# Extruder_Board2_0_0.net
KiCad netlist of a schematic drawn in EAGLE
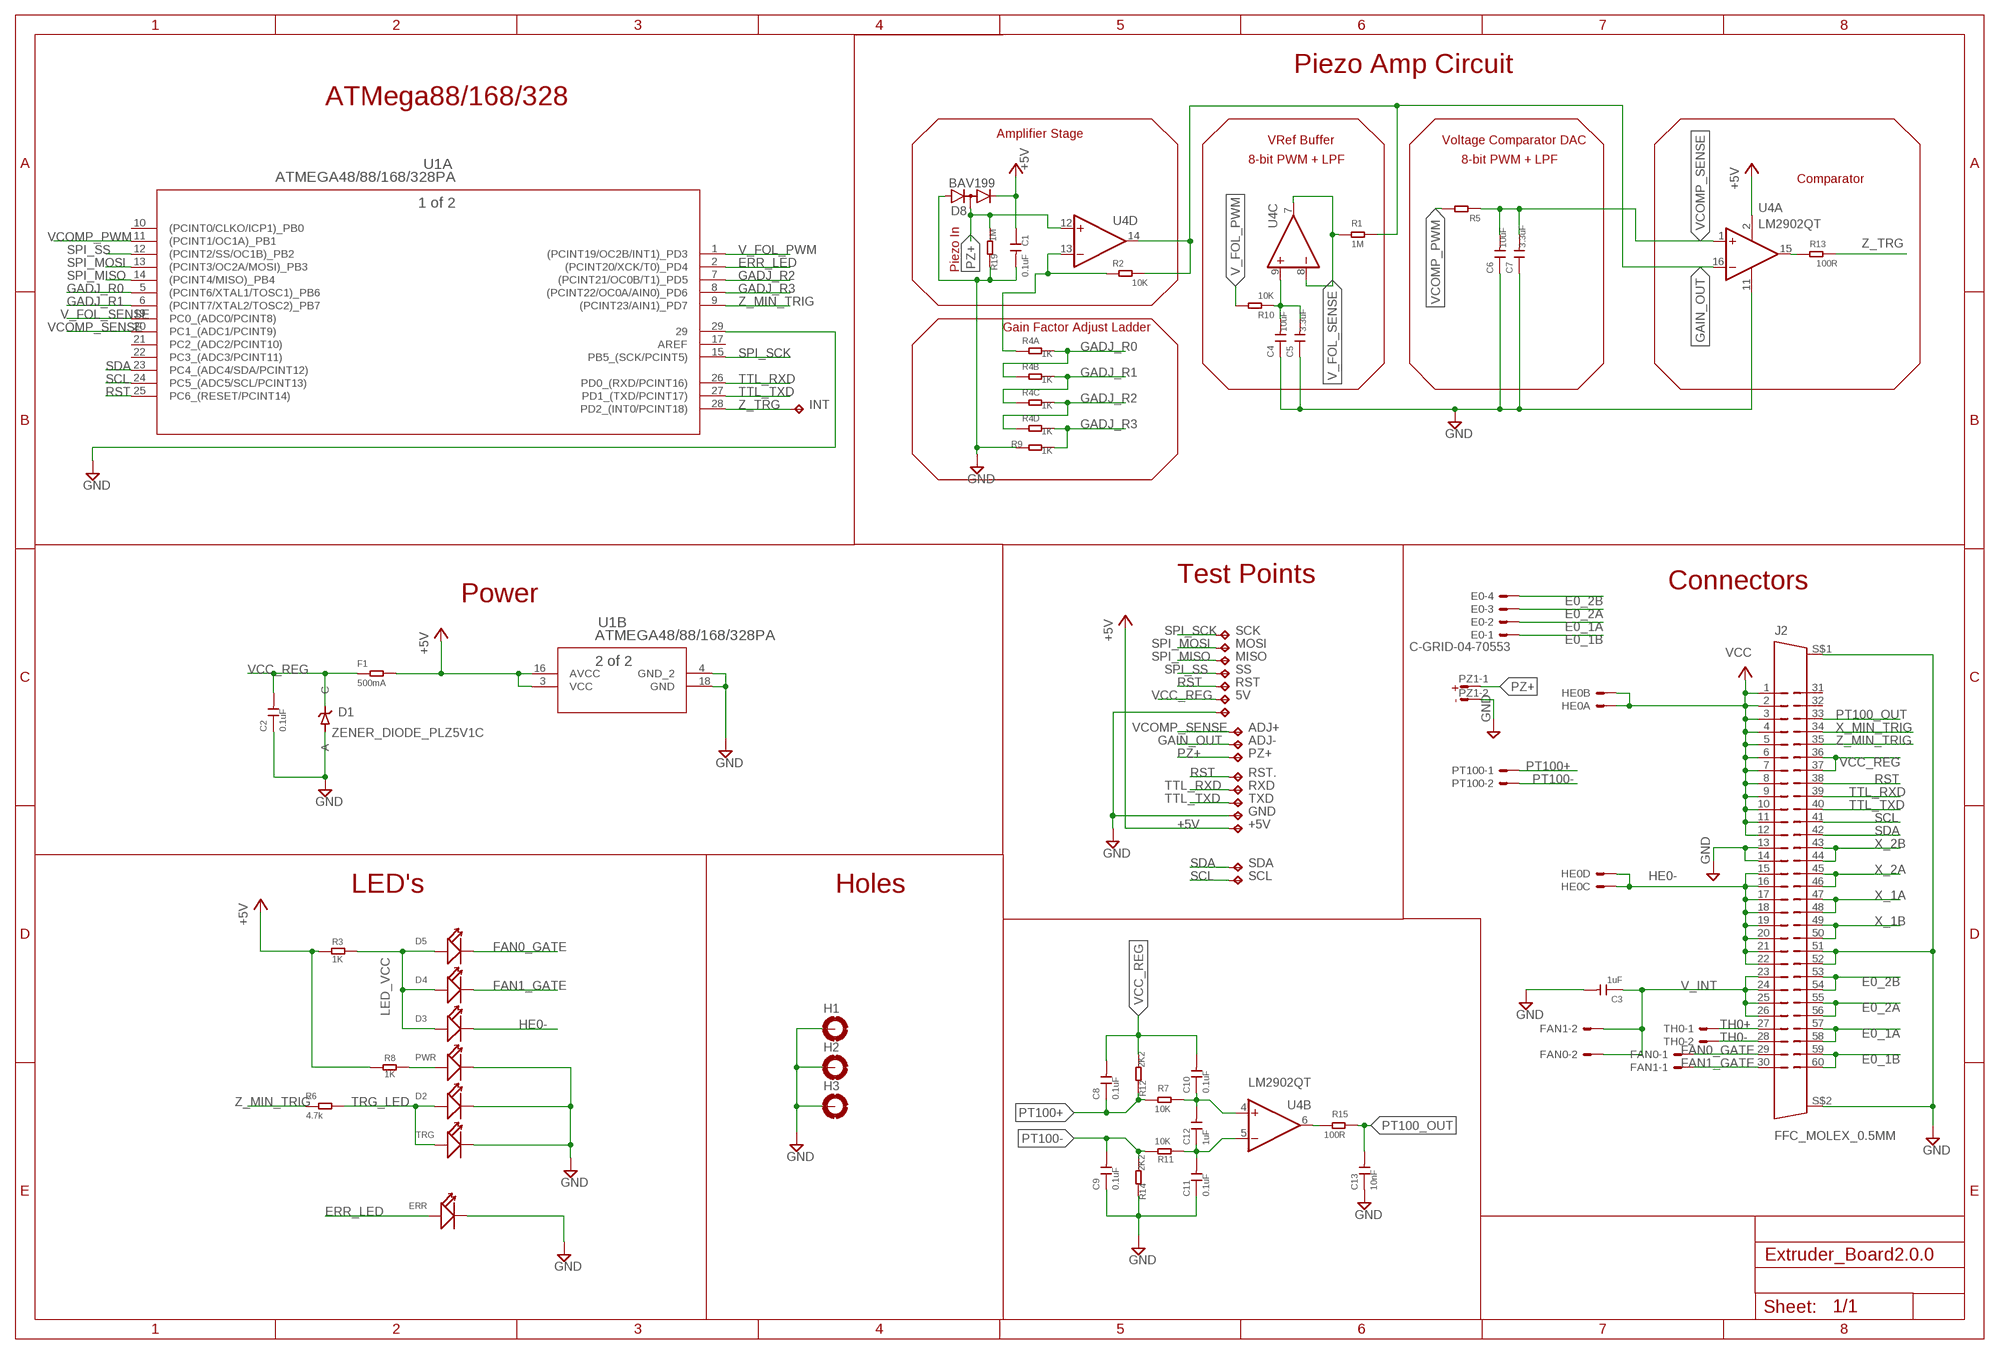
[diagram p0: schematic, sheet 1]

(export (version "E")
  (design (tool "Eeschema 10.0.6"))
  (components
    (comp (ref "+5V")
      (value "TPTP13SQ")
      (footprint "eagle-import:TP13SQ")
      (libsource (lib "eagle-import") (part "testpad_385_TPTP13SQ"))
    )
    (comp (ref "5V")
      (value "TPTP13SQ")
      (footprint "eagle-import:TP13SQ")
      (libsource (lib "eagle-import") (part "TPTP13SQ"))
    )
    (comp (ref "ADJ+")
      (value "TPTP13SQ")
      (footprint "eagle-import:TP13SQ")
      (libsource (lib "eagle-import") (part "TPTP13SQ"))
    )
    (comp (ref "ADJ-")
      (value "TPTP13SQ")
      (footprint "eagle-import:TP13SQ")
      (libsource (lib "eagle-import") (part "TPTP13SQ"))
    )
    (comp (ref "C1")
      (value "0.1uF")
      (footprint "eagle-import:CAPC1005X50")
      (libsource (lib "eagle-import") (part "CERAMIC-1NF-50V-10%-X7R(0402)CAP_0402"))
    )
    (comp (ref "C2")
      (value "0.1uF")
      (footprint "eagle-import:CAPC1005X50")
      (libsource (lib "eagle-import") (part "CERAMIC-1NF-50V-10%-X7R(0402)CAP_0402"))
    )
    (comp (ref "C3")
      (value "1uF")
      (footprint "eagle-import:CAPC1609X80")
      (libsource (lib "eagle-import") (part "SEEED-CAPACITOR_CERAMIC-10UF-25V-10%-X5R(0805)CAP_0603_GEN"))
    )
    (comp (ref "C4")
      (value "10uF")
      (footprint "eagle-import:CAPC1005X50")
      (libsource (lib "eagle-import") (part "CERAMIC-1NF-50V-10%-X7R(0402)CAP_0402"))
    )
    (comp (ref "C5")
      (value "3.3uF")
      (footprint "eagle-import:CAPC1609X80")
      (libsource (lib "eagle-import") (part "SEEED-CAPACITOR_CERAMIC-10UF-25V-10%-X5R(0805)CAP_0603_GEN"))
    )
    (comp (ref "C6")
      (value "10uF")
      (footprint "eagle-import:CAPC1005X50")
      (libsource (lib "eagle-import") (part "CERAMIC-1NF-50V-10%-X7R(0402)CAP_0402"))
    )
    (comp (ref "C7")
      (value "3.3uF")
      (footprint "eagle-import:CAPC1609X80")
      (libsource (lib "eagle-import") (part "SEEED-CAPACITOR_CERAMIC-10UF-25V-10%-X5R(0805)CAP_0603_GEN"))
    )
    (comp (ref "C8")
      (value "0.1uF")
      (footprint "eagle-import:CAPC1005X50")
      (libsource (lib "eagle-import") (part "CERAMIC-1NF-50V-10%-X7R(0402)CAP_0402"))
    )
    (comp (ref "C9")
      (value "0.1uF")
      (footprint "eagle-import:CAPC1005X50")
      (libsource (lib "eagle-import") (part "CERAMIC-1NF-50V-10%-X7R(0402)CAP_0402"))
    )
    (comp (ref "C10")
      (value "0.1uF")
      (footprint "eagle-import:CAPC1005X50")
      (libsource (lib "eagle-import") (part "CERAMIC-1NF-50V-10%-X7R(0402)CAP_0402"))
    )
    (comp (ref "C11")
      (value "0.1uF")
      (footprint "eagle-import:CAPC1005X50")
      (libsource (lib "eagle-import") (part "CERAMIC-1NF-50V-10%-X7R(0402)CAP_0402"))
    )
    (comp (ref "C12")
      (value "1uF")
      (footprint "eagle-import:CAPC1005X50")
      (libsource (lib "eagle-import") (part "CERAMIC-1NF-50V-10%-X7R(0402)CAP_0402"))
    )
    (comp (ref "C13")
      (value "10nF")
      (footprint "eagle-import:CAPC1005X50")
      (libsource (lib "eagle-import") (part "CERAMIC-1NF-50V-10%-X7R(0402)CAP_0402"))
    )
    (comp (ref "D1")
      (value "ZENER_DIODE_PLZ5V1C")
      (footprint "eagle-import:DO-219AC")
      (libsource (lib "eagle-import") (part "ZENER_DIODE_PLZ5V1C"))
    )
    (comp (ref "D2")
      (value "SEEED-LED_SMD-LED-CLEAR-BLUE(0603)LED_0603")
      (footprint "eagle-import:SEEED-LED_LED-0603")
      (libsource (lib "eagle-import") (part "SEEED-LED_SMD-LED-CLEAR-BLUE(0603)LED_0603"))
    )
    (comp (ref "D3")
      (value "SEEED-LED_SMD-LED-CLEAR-BLUE(0603)LED_0603")
      (footprint "eagle-import:SEEED-LED_LED-0603")
      (libsource (lib "eagle-import") (part "SEEED-LED_SMD-LED-CLEAR-BLUE(0603)LED_0603"))
    )
    (comp (ref "D4")
      (value "SEEED-LED_SMD-LED-CLEAR-BLUE(0603)LED_0603")
      (footprint "eagle-import:SEEED-LED_LED-0603")
      (libsource (lib "eagle-import") (part "SEEED-LED_SMD-LED-CLEAR-BLUE(0603)LED_0603"))
    )
    (comp (ref "D5")
      (value "SEEED-LED_SMD-LED-CLEAR-BLUE(0603)LED_0603")
      (footprint "eagle-import:SEEED-LED_LED-0603")
      (libsource (lib "eagle-import") (part "SEEED-LED_SMD-LED-CLEAR-BLUE(0603)LED_0603"))
    )
    (comp (ref "D8")
      (value "BAV199")
      (footprint "eagle-import:SOT23")
      (libsource (lib "eagle-import") (part "BAV199"))
    )
    (comp (ref "E0")
      (value "C-GRID-04-70553")
      (footprint "eagle-import:70553-04")
      (fields (field (name "MF") "MOLEX"))
      (libsource (lib "eagle-import") (part "C-GRID-04-70553"))
    )
    (comp (ref "ERR")
      (value "SEEED-LED_SMD-LED-CLEAR-BLUE(0603)LED_0603")
      (footprint "eagle-import:SEEED-LED_LED-0603")
      (libsource (lib "eagle-import") (part "SEEED-LED_SMD-LED-CLEAR-BLUE(0603)LED_0603"))
    )
    (comp (ref "F1")
      (value "500mA")
      (footprint "eagle-import:SEEED-RESISTOR_R0603")
      (libsource (lib "eagle-import") (part "SEEED-RESISTOR_SMD-RES-1.5K-1%-1/10W(0603)DETAILED_MODEL"))
    )
    (comp (ref "FAN0")
      (value "CON-MOLEX-2P-1.27MM048")
      (footprint "eagle-import:53048-02")
      (fields (field (name "MF") "MOLEX") (field (name "MPN") "53048-0210"))
      (libsource (lib "eagle-import") (part "CON-MOLEX-2P-1.27MM048"))
    )
    (comp (ref "FAN1")
      (value "CON-MOLEX-2P-1.27MM048")
      (footprint "eagle-import:53048-02")
      (fields (field (name "MF") "MOLEX") (field (name "MPN") "53048-0210"))
      (libsource (lib "eagle-import") (part "CON-MOLEX-2P-1.27MM048"))
    )
    (comp (ref "GND")
      (value "TPTP13SQ")
      (footprint "eagle-import:TP13SQ")
      (libsource (lib "eagle-import") (part "testpad_385_TPTP13SQ"))
    )
    (comp (ref "H1")
      (value "HOLES_MOUNT-PAD-ROUND3.2")
      (footprint "eagle-import:HOLES_3,2-PAD")
      (libsource (lib "eagle-import") (part "HOLES_MOUNT-PAD-ROUND3.2"))
    )
    (comp (ref "H2")
      (value "HOLES_MOUNT-PAD-ROUND3.2")
      (footprint "eagle-import:HOLES_3,2-PAD")
      (libsource (lib "eagle-import") (part "HOLES_MOUNT-PAD-ROUND3.2"))
    )
    (comp (ref "H3")
      (value "HOLES_MOUNT-PAD-ROUND3.2")
      (footprint "eagle-import:HOLES_3,2-PAD")
      (libsource (lib "eagle-import") (part "HOLES_MOUNT-PAD-ROUND3.2"))
    )
    (comp (ref "HE0")
      (value "JST-2.54-2X2JST-DUPONT-2.54-2X2")
      (footprint "eagle-import:HDRRAR4W64P254_2X2_556X736X556B")
      (libsource (lib "eagle-import") (part "JST-2.54-2X2JST-DUPONT-2.54-2X2"))
    )
    (comp (ref "INT")
      (value "TPTP06R")
      (footprint "eagle-import:TP06R")
      (libsource (lib "eagle-import") (part "testpad_385_TPTP06R"))
    )
    (comp (ref "J2")
      (value "FFC_MOLEX_0.5MM")
      (footprint "eagle-import:FFC-60P_0.5_MOLEX_505110-6091")
      (libsource (lib "eagle-import") (part "FFC_MOLEX_0.5MM"))
    )
    (comp (ref "MISO")
      (value "TPTP13SQ")
      (footprint "eagle-import:TP13SQ")
      (libsource (lib "eagle-import") (part "TPTP13SQ"))
    )
    (comp (ref "MOSI")
      (value "TPTP13SQ")
      (footprint "eagle-import:TP13SQ")
      (libsource (lib "eagle-import") (part "TPTP13SQ"))
    )
    (comp (ref "PT100")
      (value "CON-MOLEX-2P-1.27MM048")
      (footprint "eagle-import:53048-02")
      (fields (field (name "MF") "MOLEX") (field (name "MPN") "53048-0210"))
      (libsource (lib "eagle-import") (part "CON-MOLEX-2P-1.27MM048"))
    )
    (comp (ref "PWR")
      (value "SEEED-LED_SMD-LED-CLEAR-BLUE(0603)LED_0603")
      (footprint "eagle-import:SEEED-LED_LED-0603")
      (libsource (lib "eagle-import") (part "SEEED-LED_SMD-LED-CLEAR-BLUE(0603)LED_0603"))
    )
    (comp (ref "PZ+")
      (value "TPTP13SQ")
      (footprint "eagle-import:TP13SQ")
      (libsource (lib "eagle-import") (part "TPTP13SQ"))
    )
    (comp (ref "PZ1")
      (value "CON-MOLEX-2P-1.27MM048")
      (footprint "eagle-import:53048-02")
      (fields (field (name "MF") "MOLEX") (field (name "MPN") "53048-0210"))
      (libsource (lib "eagle-import") (part "CON-MOLEX-2P-1.27MM048"))
    )
    (comp (ref "R1")
      (value "1M")
      (footprint "eagle-import:R0402")
      (fields (field (name "MPN") "RC0402JR-070RL"))
      (libsource (lib "eagle-import") (part "SMD-RES-0R-5%-1/16W(0402)"))
    )
    (comp (ref "R2")
      (value "10K")
      (footprint "eagle-import:R0402")
      (fields (field (name "MPN") "RC0402JR-070RL"))
      (libsource (lib "eagle-import") (part "SMD-RES-0R-5%-1/16W(0402)"))
    )
    (comp (ref "R3")
      (value "1K")
      (footprint "eagle-import:R0402")
      (fields (field (name "MPN") "RC0402JR-070RL"))
      (libsource (lib "eagle-import") (part "SMD-RES-0R-5%-1/16W(0402)"))
    )
    (comp (ref "R4")
      (value "1K")
      (footprint "eagle-import:EXBN8V")
      (libsource (lib "eagle-import") (part "RESISTOR_NETWORK_X40804"))
    )
    (comp (ref "R5")
      (value "10K")
      (footprint "eagle-import:SEEED-RESISTOR_R0603")
      (libsource (lib "eagle-import") (part "SEEED-RESISTOR_SMD-RES-1.5K-1%-1/10W(0603)DETAILED_MODEL"))
    )
    (comp (ref "R6")
      (value "4.7k")
      (footprint "eagle-import:R0402")
      (fields (field (name "MPN") "RC0402JR-070RL"))
      (libsource (lib "eagle-import") (part "SMD-RES-0R-5%-1/16W(0402)"))
    )
    (comp (ref "R7")
      (value "10K")
      (footprint "eagle-import:R0402")
      (fields (field (name "MPN") "RC0402JR-070RL"))
      (libsource (lib "eagle-import") (part "SMD-RES-0R-5%-1/16W(0402)"))
    )
    (comp (ref "R8")
      (value "1K")
      (footprint "eagle-import:R0402")
      (fields (field (name "MPN") "RC0402JR-070RL"))
      (libsource (lib "eagle-import") (part "SMD-RES-0R-5%-1/16W(0402)"))
    )
    (comp (ref "R9")
      (value "1K")
      (footprint "eagle-import:R0402")
      (fields (field (name "MPN") "RC0402JR-070RL"))
      (libsource (lib "eagle-import") (part "SMD-RES-0R-5%-1/16W(0402)"))
    )
    (comp (ref "R10")
      (value "10K")
      (footprint "eagle-import:R0402")
      (fields (field (name "MPN") "RC0402JR-070RL"))
      (libsource (lib "eagle-import") (part "SMD-RES-0R-5%-1/16W(0402)"))
    )
    (comp (ref "R11")
      (value "10K")
      (footprint "eagle-import:R0402")
      (fields (field (name "MPN") "RC0402JR-070RL"))
      (libsource (lib "eagle-import") (part "SMD-RES-0R-5%-1/16W(0402)"))
    )
    (comp (ref "R12")
      (value "2K2")
      (footprint "eagle-import:R0402")
      (fields (field (name "MPN") "RC0402JR-070RL"))
      (libsource (lib "eagle-import") (part "SMD-RES-0R-5%-1/16W(0402)"))
    )
    (comp (ref "R13")
      (value "100R")
      (footprint "eagle-import:R0402")
      (fields (field (name "MPN") "RC0402JR-070RL"))
      (libsource (lib "eagle-import") (part "SMD-RES-0R-5%-1/16W(0402)"))
    )
    (comp (ref "R14")
      (value "2K2")
      (footprint "eagle-import:R0402")
      (fields (field (name "MPN") "RC0402JR-070RL"))
      (libsource (lib "eagle-import") (part "SMD-RES-0R-5%-1/16W(0402)"))
    )
    (comp (ref "R15")
      (value "100R")
      (footprint "eagle-import:R0402")
      (fields (field (name "MPN") "RC0402JR-070RL"))
      (libsource (lib "eagle-import") (part "SMD-RES-0R-5%-1/16W(0402)"))
    )
    (comp (ref "R19")
      (value "1M")
      (footprint "eagle-import:R0402")
      (fields (field (name "MPN") "RC0402JR-070RL"))
      (libsource (lib "eagle-import") (part "SMD-RES-0R-5%-1/16W(0402)"))
    )
    (comp (ref "RST")
      (value "TPTP13SQ")
      (footprint "eagle-import:TP13SQ")
      (libsource (lib "eagle-import") (part "TPTP13SQ"))
    )
    (comp (ref "RST.")
      (value "TPTP13SQ")
      (footprint "eagle-import:TP13SQ")
      (libsource (lib "eagle-import") (part "testpad_385_TPTP13SQ"))
    )
    (comp (ref "RXD")
      (value "TPTP13SQ")
      (footprint "eagle-import:TP13SQ")
      (libsource (lib "eagle-import") (part "testpad_385_TPTP13SQ"))
    )
    (comp (ref "SCK")
      (value "TPTP13SQ")
      (footprint "eagle-import:TP13SQ")
      (libsource (lib "eagle-import") (part "TPTP13SQ"))
    )
    (comp (ref "SCL")
      (value "TPTP13SQ")
      (footprint "eagle-import:TP13SQ")
      (libsource (lib "eagle-import") (part "testpad_385_TPTP13SQ"))
    )
    (comp (ref "SDA")
      (value "TPTP13SQ")
      (footprint "eagle-import:TP13SQ")
      (libsource (lib "eagle-import") (part "testpad_385_TPTP13SQ"))
    )
    (comp (ref "SS")
      (value "TPTP06R")
      (footprint "eagle-import:TP06R")
      (libsource (lib "eagle-import") (part "testpad_385_TPTP06R"))
    )
    (comp (ref "TH0")
      (value "CON-MOLEX-2P-1.27MM048")
      (footprint "eagle-import:53048-02")
      (fields (field (name "MF") "MOLEX") (field (name "MPN") "53048-0210"))
      (libsource (lib "eagle-import") (part "CON-MOLEX-2P-1.27MM048"))
    )
    (comp (ref "TRG")
      (value "SEEED-LED_SMD-LED-CLEAR-BLUE(0603)LED_0603")
      (footprint "eagle-import:SEEED-LED_LED-0603")
      (libsource (lib "eagle-import") (part "SEEED-LED_SMD-LED-CLEAR-BLUE(0603)LED_0603"))
    )
    (comp (ref "TXD")
      (value "TPTP13SQ")
      (footprint "eagle-import:TP13SQ")
      (libsource (lib "eagle-import") (part "testpad_385_TPTP13SQ"))
    )
    (comp (ref "U1")
      (value "ATMEGA48/88/168/328PA")
      (footprint "eagle-import:28M1")
      (fields (field (name "MANUFACTURER_PART_NUMBER") "ATMEGA48PAMMHR"))
      (libsource (lib "eagle-import") (part "ATMEGA48/88/168/328PA"))
    )
    (comp (ref "U4")
      (value "LM2902QT")
      (footprint "eagle-import:QFN16")
      (libsource (lib "eagle-import") (part "LM2902QT"))
    )
    (comp (ref "⏚")
      (value "TPTP13SQ")
      (footprint "eagle-import:TP13SQ")
      (libsource (lib "eagle-import") (part "testpad_385_TPTP13SQ"))
    )
  )
  (nets
    (net (code "1") (name "+5V") (class "Default")
      (node (ref "+5V") (pin "TP") (pinfunction "TP_TP") (pintype "input"))
      (node (ref "C1") (pin "1") (pinfunction "1_1") (pintype "passive"))
      (node (ref "D8") (pin "2") (pinfunction "C_2") (pintype "passive"))
      (node (ref "F1") (pin "2") (pinfunction "2_2") (pintype "passive"))
      (node (ref "R3") (pin "1") (pinfunction "1_1") (pintype "passive"))
      (node (ref "R8") (pin "1") (pinfunction "1_1") (pintype "passive"))
      (node (ref "U1") (pin "16") (pinfunction "AVCC_16") (pintype "power_in"))
      (node (ref "U1") (pin "3") (pinfunction "VCC_3") (pintype "power_in"))
      (node (ref "U4") (pin "2") (pinfunction "V+_2") (pintype "power_in"))
    )
    (net (code "2") (name "/E0_1A") (class "Default")
      (node (ref "E0") (pin "2") (pinfunction "S_2") (pintype "passive"))
      (node (ref "J2") (pin "57") (pinfunction "63_57") (pintype "passive"))
      (node (ref "J2") (pin "58") (pinfunction "64_58") (pintype "passive"))
    )
    (net (code "3") (name "/E0_1B") (class "Default")
      (node (ref "E0") (pin "1") (pinfunction "S_1") (pintype "passive"))
      (node (ref "J2") (pin "59") (pinfunction "65_59") (pintype "passive"))
      (node (ref "J2") (pin "60") (pinfunction "66_60") (pintype "passive"))
    )
    (net (code "4") (name "/E0_2A") (class "Default")
      (node (ref "E0") (pin "3") (pinfunction "S_3") (pintype "passive"))
      (node (ref "J2") (pin "55") (pinfunction "61_55") (pintype "passive"))
      (node (ref "J2") (pin "56") (pinfunction "62_56") (pintype "passive"))
    )
    (net (code "5") (name "/E0_2B") (class "Default")
      (node (ref "E0") (pin "4") (pinfunction "S_4") (pintype "passive"))
      (node (ref "J2") (pin "53") (pinfunction "59_53") (pintype "passive"))
      (node (ref "J2") (pin "54") (pinfunction "60_54") (pintype "passive"))
    )
    (net (code "6") (name "/ERR_LED") (class "Default")
      (node (ref "ERR") (pin "+") (pinfunction "+_+") (pintype "passive"))
      (node (ref "U1") (pin "2") (pinfunction "(PCINT20/XCK/T0)_PD4_2") (pintype "bidirectional"))
    )
    (net (code "7") (name "/FAN0_GATE") (class "Default")
      (node (ref "D5") (pin "-") (pinfunction "-_-") (pintype "passive"))
      (node (ref "FAN0") (pin "1") (pinfunction "S_1") (pintype "passive"))
      (node (ref "J2") (pin "29") (pinfunction "31_29") (pintype "passive"))
    )
    (net (code "8") (name "/FAN1_GATE") (class "Default")
      (node (ref "D4") (pin "-") (pinfunction "-_-") (pintype "passive"))
      (node (ref "FAN1") (pin "1") (pinfunction "S_1") (pintype "passive"))
      (node (ref "J2") (pin "30") (pinfunction "32_30") (pintype "passive"))
    )
    (net (code "9") (name "/GADJ_R0") (class "Default")
      (node (ref "R4") (pin "2") (pinfunction "1_2") (pintype "passive"))
      (node (ref "R4") (pin "8") (pinfunction "2_8") (pintype "passive"))
      (node (ref "U1") (pin "5") (pinfunction "(PCINT6/XTAL1/TOSC1)_PB6_5") (pintype "bidirectional"))
    )
    (net (code "10") (name "/GADJ_R1") (class "Default")
      (node (ref "R4") (pin "3") (pinfunction "1_3") (pintype "passive"))
      (node (ref "R4") (pin "7") (pinfunction "2_7") (pintype "passive"))
      (node (ref "U1") (pin "6") (pinfunction "(PCINT7/XTAL2/TOSC2)_PB7_6") (pintype "bidirectional"))
    )
    (net (code "11") (name "/GADJ_R2") (class "Default")
      (node (ref "R4") (pin "4") (pinfunction "1_4") (pintype "passive"))
      (node (ref "R4") (pin "6") (pinfunction "2_6") (pintype "passive"))
      (node (ref "U1") (pin "7") (pinfunction "(PCINT21/OC0B/T1)_PD5_7") (pintype "bidirectional"))
    )
    (net (code "12") (name "/GADJ_R3") (class "Default")
      (node (ref "R4") (pin "5") (pinfunction "2_5") (pintype "passive"))
      (node (ref "R9") (pin "2") (pinfunction "2_2") (pintype "passive"))
      (node (ref "U1") (pin "8") (pinfunction "(PCINT22/OC0A/AIN0)_PD6_8") (pintype "bidirectional"))
    )
    (net (code "13") (name "/HE0-") (class "Default")
      (node (ref "D3") (pin "-") (pinfunction "-_-") (pintype "passive"))
      (node (ref "HE0") (pin "3") (pinfunction "S_3") (pintype "passive"))
      (node (ref "HE0") (pin "4") (pinfunction "S_4") (pintype "passive"))
      (node (ref "J2") (pin "15") (pinfunction "17_15") (pintype "passive"))
      (node (ref "J2") (pin "16") (pinfunction "18_16") (pintype "passive"))
      (node (ref "J2") (pin "17") (pinfunction "19_17") (pintype "passive"))
      (node (ref "J2") (pin "18") (pinfunction "20_18") (pintype "passive"))
      (node (ref "J2") (pin "19") (pinfunction "21_19") (pintype "passive"))
      (node (ref "J2") (pin "20") (pinfunction "22_20") (pintype "passive"))
      (node (ref "J2") (pin "21") (pinfunction "23_21") (pintype "passive"))
      (node (ref "J2") (pin "22") (pinfunction "24_22") (pintype "passive"))
    )
    (net (code "14") (name "/LED_VCC") (class "Default")
      (node (ref "D3") (pin "+") (pinfunction "+_+") (pintype "passive"))
      (node (ref "D4") (pin "+") (pinfunction "+_+") (pintype "passive"))
      (node (ref "D5") (pin "+") (pinfunction "+_+") (pintype "passive"))
      (node (ref "R3") (pin "2") (pinfunction "2_2") (pintype "passive"))
    )
    (net (code "15") (name "/RST") (class "Default")
      (node (ref "J2") (pin "38") (pinfunction "44_38") (pintype "passive"))
      (node (ref "RST") (pin "TP") (pinfunction "TP_TP") (pintype "input"))
      (node (ref "RST.") (pin "TP") (pinfunction "TP_TP") (pintype "input"))
      (node (ref "U1") (pin "25") (pinfunction "PC6_(RESET/PCINT14)_25") (pintype "bidirectional"))
    )
    (net (code "16") (name "/SCL") (class "Default")
      (node (ref "J2") (pin "41") (pinfunction "47_41") (pintype "passive"))
      (node (ref "SCL") (pin "TP") (pinfunction "TP_TP") (pintype "input"))
      (node (ref "U1") (pin "24") (pinfunction "PC5_(ADC5/SCL/PCINT13)_24") (pintype "bidirectional"))
    )
    (net (code "17") (name "/SDA") (class "Default")
      (node (ref "J2") (pin "42") (pinfunction "48_42") (pintype "passive"))
      (node (ref "SDA") (pin "TP") (pinfunction "TP_TP") (pintype "input"))
      (node (ref "U1") (pin "23") (pinfunction "PC4_(ADC4/SDA/PCINT12)_23") (pintype "bidirectional"))
    )
    (net (code "18") (name "/SPI_MISO") (class "Default")
      (node (ref "MISO") (pin "TP") (pinfunction "TP_TP") (pintype "input"))
      (node (ref "U1") (pin "14") (pinfunction "(PCINT4/MISO)_PB4_14") (pintype "bidirectional"))
    )
    (net (code "19") (name "/SPI_MOSI") (class "Default")
      (node (ref "MOSI") (pin "TP") (pinfunction "TP_TP") (pintype "input"))
      (node (ref "U1") (pin "13") (pinfunction "(PCINT3/OC2A/MOSI)_PB3_13") (pintype "bidirectional"))
    )
    (net (code "20") (name "/SPI_SCK") (class "Default")
      (node (ref "SCK") (pin "TP") (pinfunction "TP_TP") (pintype "input"))
      (node (ref "U1") (pin "15") (pinfunction "PB5_(SCK/PCINT5)_15") (pintype "bidirectional"))
    )
    (net (code "21") (name "/SPI_SS") (class "Default")
      (node (ref "SS") (pin "TP") (pinfunction "TP_TP") (pintype "input"))
      (node (ref "U1") (pin "12") (pinfunction "(PCINT2/SS/OC1B)_PB2_12") (pintype "bidirectional"))
    )
    (net (code "22") (name "/TH0+") (class "Default")
      (node (ref "J2") (pin "27") (pinfunction "29_27") (pintype "passive"))
      (node (ref "TH0") (pin "1") (pinfunction "S_1") (pintype "passive"))
    )
    (net (code "23") (name "/TH0-") (class "Default")
      (node (ref "J2") (pin "28") (pinfunction "30_28") (pintype "passive"))
      (node (ref "TH0") (pin "2") (pinfunction "S_2") (pintype "passive"))
    )
    (net (code "24") (name "/TRG_LED") (class "Default")
      (node (ref "D2") (pin "+") (pinfunction "+_+") (pintype "passive"))
      (node (ref "R6") (pin "2") (pinfunction "2_2") (pintype "passive"))
      (node (ref "TRG") (pin "+") (pinfunction "+_+") (pintype "passive"))
    )
    (net (code "25") (name "/TTL_RXD") (class "Default")
      (node (ref "J2") (pin "39") (pinfunction "45_39") (pintype "passive"))
      (node (ref "RXD") (pin "TP") (pinfunction "TP_TP") (pintype "input"))
      (node (ref "U1") (pin "26") (pinfunction "PD0_(RXD/PCINT16)_26") (pintype "bidirectional"))
    )
    (net (code "26") (name "/TTL_TXD") (class "Default")
      (node (ref "J2") (pin "40") (pinfunction "46_40") (pintype "passive"))
      (node (ref "TXD") (pin "TP") (pinfunction "TP_TP") (pintype "input"))
      (node (ref "U1") (pin "27") (pinfunction "PD1_(TXD/PCINT17)_27") (pintype "bidirectional"))
    )
    (net (code "27") (name "/V_INT") (class "Default")
      (node (ref "C3") (pin "1") (pinfunction "1_1") (pintype "passive"))
      (node (ref "FAN0") (pin "2") (pinfunction "S_2") (pintype "passive"))
      (node (ref "FAN1") (pin "2") (pinfunction "S_2") (pintype "passive"))
      (node (ref "J2") (pin "23") (pinfunction "25_23") (pintype "passive"))
      (node (ref "J2") (pin "24") (pinfunction "26_24") (pintype "passive"))
      (node (ref "J2") (pin "25") (pinfunction "27_25") (pintype "passive"))
      (node (ref "J2") (pin "26") (pinfunction "28_26") (pintype "passive"))
    )
    (net (code "28") (name "/X_1A") (class "Default")
      (node (ref "J2") (pin "47") (pinfunction "53_47") (pintype "passive"))
      (node (ref "J2") (pin "48") (pinfunction "54_48") (pintype "passive"))
    )
    (net (code "29") (name "/X_1B") (class "Default")
      (node (ref "J2") (pin "49") (pinfunction "55_49") (pintype "passive"))
      (node (ref "J2") (pin "50") (pinfunction "56_50") (pintype "passive"))
    )
    (net (code "30") (name "/X_2A") (class "Default")
      (node (ref "J2") (pin "45") (pinfunction "51_45") (pintype "passive"))
      (node (ref "J2") (pin "46") (pinfunction "52_46") (pintype "passive"))
    )
    (net (code "31") (name "/X_2B") (class "Default")
      (node (ref "J2") (pin "43") (pinfunction "49_43") (pintype "passive"))
      (node (ref "J2") (pin "44") (pinfunction "50_44") (pintype "passive"))
    )
    (net (code "32") (name "/X_MIN_TRIG") (class "Default")
      (node (ref "J2") (pin "34") (pinfunction "40_34") (pintype "passive"))
    )
    (net (code "33") (name "/Z_MIN_TRIG") (class "Default")
      (node (ref "J2") (pin "35") (pinfunction "41_35") (pintype "passive"))
      (node (ref "R6") (pin "1") (pinfunction "1_1") (pintype "passive"))
      (node (ref "U1") (pin "9") (pinfunction "(PCINT23/AIN1)_PD7_9") (pintype "bidirectional"))
    )
    (net (code "34") (name "/Z_TRG") (class "Default")
      (node (ref "INT") (pin "TP") (pinfunction "TP_TP") (pintype "input"))
      (node (ref "R13") (pin "2") (pinfunction "2_2") (pintype "passive"))
      (node (ref "U1") (pin "28") (pinfunction "PD2_(INT0/PCINT18)_28") (pintype "bidirectional"))
    )
    (net (code "35") (name "GAIN_OUT") (class "Default")
      (node (ref "ADJ-") (pin "TP") (pinfunction "TP_TP") (pintype "input"))
      (node (ref "R1") (pin "2") (pinfunction "2_2") (pintype "passive"))
      (node (ref "R2") (pin "2") (pinfunction "2_2") (pintype "passive"))
      (node (ref "U4") (pin "14") (pinfunction "OUT_14") (pintype "output"))
      (node (ref "U4") (pin "16") (pinfunction "-IN_16") (pintype "input"))
    )
    (net (code "36") (name "GND") (class "Default")
      (node (ref "C1") (pin "2") (pinfunction "2_2") (pintype "passive"))
      (node (ref "C11") (pin "1") (pinfunction "1_1") (pintype "passive"))
      (node (ref "C13") (pin "1") (pinfunction "1_1") (pintype "passive"))
      (node (ref "C2") (pin "1") (pinfunction "1_1") (pintype "passive"))
      (node (ref "C3") (pin "2") (pinfunction "2_2") (pintype "passive"))
      (node (ref "C4") (pin "1") (pinfunction "1_1") (pintype "passive"))
      (node (ref "C5") (pin "1") (pinfunction "1_1") (pintype "passive"))
      (node (ref "C6") (pin "1") (pinfunction "1_1") (pintype "passive"))
      (node (ref "C7") (pin "1") (pinfunction "1_1") (pintype "passive"))
      (node (ref "C9") (pin "1") (pinfunction "1_1") (pintype "passive"))
      (node (ref "D1") (pin "P$1") (pinfunction "A_P$1") (pintype "passive"))
      (node (ref "D2") (pin "-") (pinfunction "-_-") (pintype "passive"))
      (node (ref "D8") (pin "1") (pinfunction "A_1") (pintype "passive"))
      (node (ref "ERR") (pin "-") (pinfunction "-_-") (pintype "passive"))
      (node (ref "GND") (pin "TP") (pinfunction "TP_TP") (pintype "input"))
      (node (ref "H1") (pin "B3,2") (pinfunction "MOUNT_B3,2") (pintype "passive"))
      (node (ref "H2") (pin "B3,2") (pinfunction "MOUNT_B3,2") (pintype "passive"))
      (node (ref "H3") (pin "B3,2") (pinfunction "MOUNT_B3,2") (pintype "passive"))
      (node (ref "J2") (pin "13") (pinfunction "15_13") (pintype "passive"))
      (node (ref "J2") (pin "14") (pinfunction "16_14") (pintype "passive"))
      (node (ref "J2") (pin "51") (pinfunction "57_51") (pintype "passive"))
      (node (ref "J2") (pin "52") (pinfunction "58_52") (pintype "passive"))
      (node (ref "J2") (pin "S$1") (pinfunction "S_S$1") (pintype "passive"))
      (node (ref "J2") (pin "S$2") (pinfunction "S_S$2") (pintype "passive"))
      (node (ref "PWR") (pin "-") (pinfunction "-_-") (pintype "passive"))
      (node (ref "PZ1") (pin "2") (pinfunction "S_2") (pintype "passive"))
      (node (ref "R14") (pin "1") (pinfunction "1_1") (pintype "passive"))
      (node (ref "R19") (pin "1") (pinfunction "1_1") (pintype "passive"))
      (node (ref "R9") (pin "1") (pinfunction "1_1") (pintype "passive"))
      (node (ref "TRG") (pin "-") (pinfunction "-_-") (pintype "passive"))
      (node (ref "U1") (pin "18") (pinfunction "GND_18") (pintype "power_in"))
      (node (ref "U1") (pin "29") (pinfunction "29_29") (pintype "passive"))
      (node (ref "U1") (pin "4") (pinfunction "GND_2_4") (pintype "power_in"))
      (node (ref "U4") (pin "11") (pinfunction "V-_11") (pintype "power_in"))
      (node (ref "⏚") (pin "TP") (pinfunction "TP_TP") (pintype "input"))
    )
    (net (code "37") (name "Net-(PWR-Pad+)") (class "Default")
      (node (ref "PWR") (pin "+") (pinfunction "+_+") (pintype "passive"))
      (node (ref "R8") (pin "2") (pinfunction "2_2") (pintype "passive"))
    )
    (net (code "38") (name "Net-(U4A-OUT)") (class "Default")
      (node (ref "R13") (pin "1") (pinfunction "1_1") (pintype "passive"))
      (node (ref "U4") (pin "15") (pinfunction "OUT_15") (pintype "output"))
    )
    (net (code "39") (name "Net-(U4B-+IN)") (class "Default")
      (node (ref "C10") (pin "1") (pinfunction "1_1") (pintype "passive"))
      (node (ref "C12") (pin "2") (pinfunction "2_2") (pintype "passive"))
      (node (ref "R7") (pin "1") (pinfunction "1_1") (pintype "passive"))
      (node (ref "U4") (pin "4") (pinfunction "+IN_4") (pintype "input"))
    )
    (net (code "40") (name "Net-(U4B--IN)") (class "Default")
      (node (ref "C11") (pin "2") (pinfunction "2_2") (pintype "passive"))
      (node (ref "C12") (pin "1") (pinfunction "1_1") (pintype "passive"))
      (node (ref "R11") (pin "1") (pinfunction "1_1") (pintype "passive"))
      (node (ref "U4") (pin "5") (pinfunction "-IN_5") (pintype "input"))
    )
    (net (code "41") (name "Net-(U4B-OUT)") (class "Default")
      (node (ref "R15") (pin "2") (pinfunction "2_2") (pintype "passive"))
      (node (ref "U4") (pin "6") (pinfunction "OUT_6") (pintype "output"))
    )
    (net (code "42") (name "Net-(U4C-+IN)") (class "Default")
      (node (ref "C4") (pin "2") (pinfunction "2_2") (pintype "passive"))
      (node (ref "C5") (pin "2") (pinfunction "2_2") (pintype "passive"))
      (node (ref "R10") (pin "1") (pinfunction "1_1") (pintype "passive"))
      (node (ref "U4") (pin "9") (pinfunction "+IN_9") (pintype "input"))
    )
    (net (code "43") (name "Net-(U4D--IN)") (class "Default")
      (node (ref "R2") (pin "1") (pinfunction "1_1") (pintype "passive"))
      (node (ref "R4") (pin "1") (pinfunction "1_1") (pintype "passive"))
      (node (ref "U4") (pin "13") (pinfunction "-IN_13") (pintype "input"))
    )
    (net (code "44") (name "PT100+") (class "Default")
      (node (ref "C8") (pin "1") (pinfunction "1_1") (pintype "passive"))
      (node (ref "PT100") (pin "1") (pinfunction "S_1") (pintype "passive"))
      (node (ref "R12") (pin "1") (pinfunction "1_1") (pintype "passive"))
      (node (ref "R7") (pin "2") (pinfunction "2_2") (pintype "passive"))
    )
    (net (code "45") (name "PT100-") (class "Default")
      (node (ref "C9") (pin "2") (pinfunction "2_2") (pintype "passive"))
      (node (ref "PT100") (pin "2") (pinfunction "S_2") (pintype "passive"))
      (node (ref "R11") (pin "2") (pinfunction "2_2") (pintype "passive"))
      (node (ref "R14") (pin "2") (pinfunction "2_2") (pintype "passive"))
    )
    (net (code "46") (name "PT100_OUT") (class "Default")
      (node (ref "C13") (pin "2") (pinfunction "2_2") (pintype "passive"))
      (node (ref "J2") (pin "33") (pinfunction "39_33") (pintype "passive"))
      (node (ref "R15") (pin "1") (pinfunction "1_1") (pintype "passive"))
    )
    (net (code "47") (name "PZ+") (class "Default")
      (node (ref "D8") (pin "3") (pinfunction "AC_3") (pintype "passive"))
      (node (ref "PZ+") (pin "TP") (pinfunction "TP_TP") (pintype "input"))
      (node (ref "PZ1") (pin "1") (pinfunction "S_1") (pintype "passive"))
      (node (ref "R19") (pin "2") (pinfunction "2_2") (pintype "passive"))
      (node (ref "U4") (pin "12") (pinfunction "+IN_12") (pintype "input"))
    )
    (net (code "48") (name "VCC") (class "Default")
      (node (ref "HE0") (pin "1") (pinfunction "S_1") (pintype "passive"))
      (node (ref "HE0") (pin "2") (pinfunction "S_2") (pintype "passive"))
      (node (ref "J2") (pin "1") (pinfunction "3_1") (pintype "passive"))
      (node (ref "J2") (pin "10") (pinfunction "12_10") (pintype "passive"))
      (node (ref "J2") (pin "11") (pinfunction "13_11") (pintype "passive"))
      (node (ref "J2") (pin "12") (pinfunction "14_12") (pintype "passive"))
      (node (ref "J2") (pin "2") (pinfunction "4_2") (pintype "passive"))
      (node (ref "J2") (pin "3") (pinfunction "5_3") (pintype "passive"))
      (node (ref "J2") (pin "4") (pinfunction "6_4") (pintype "passive"))
      (node (ref "J2") (pin "5") (pinfunction "7_5") (pintype "passive"))
      (node (ref "J2") (pin "6") (pinfunction "8_6") (pintype "passive"))
      (node (ref "J2") (pin "7") (pinfunction "9_7") (pintype "passive"))
      (node (ref "J2") (pin "8") (pinfunction "10_8") (pintype "passive"))
      (node (ref "J2") (pin "9") (pinfunction "11_9") (pintype "passive"))
    )
    (net (code "49") (name "VCC_REG") (class "Default")
      (node (ref "5V") (pin "TP") (pinfunction "TP_TP") (pintype "input"))
      (node (ref "C10") (pin "2") (pinfunction "2_2") (pintype "passive"))
      (node (ref "C2") (pin "2") (pinfunction "2_2") (pintype "passive"))
      (node (ref "C8") (pin "2") (pinfunction "2_2") (pintype "passive"))
      (node (ref "D1") (pin "P$2") (pinfunction "C_P$2") (pintype "passive"))
      (node (ref "F1") (pin "1") (pinfunction "1_1") (pintype "passive"))
      (node (ref "J2") (pin "36") (pinfunction "42_36") (pintype "passive"))
      (node (ref "J2") (pin "37") (pinfunction "43_37") (pintype "passive"))
      (node (ref "R12") (pin "2") (pinfunction "2_2") (pintype "passive"))
    )
    (net (code "50") (name "VCOMP_PWM") (class "Default")
      (node (ref "R5") (pin "2") (pinfunction "2_2") (pintype "passive"))
      (node (ref "U1") (pin "11") (pinfunction "(PCINT1/OC1A)_PB1_11") (pintype "bidirectional"))
    )
    (net (code "51") (name "VCOMP_SENSE") (class "Default")
      (node (ref "ADJ+") (pin "TP") (pinfunction "TP_TP") (pintype "input"))
      (node (ref "C6") (pin "2") (pinfunction "2_2") (pintype "passive"))
      (node (ref "C7") (pin "2") (pinfunction "2_2") (pintype "passive"))
      (node (ref "R5") (pin "1") (pinfunction "1_1") (pintype "passive"))
      (node (ref "U1") (pin "20") (pinfunction "PC1_(ADC1/PCINT9)_20") (pintype "bidirectional"))
      (node (ref "U4") (pin "1") (pinfunction "+IN_1") (pintype "input"))
    )
    (net (code "52") (name "V_FOL_PWM") (class "Default")
      (node (ref "R10") (pin "2") (pinfunction "2_2") (pintype "passive"))
      (node (ref "U1") (pin "1") (pinfunction "(PCINT19/OC2B/INT1)_PD3_1") (pintype "bidirectional"))
    )
    (net (code "53") (name "V_FOL_SENSE") (class "Default")
      (node (ref "R1") (pin "1") (pinfunction "1_1") (pintype "passive"))
      (node (ref "U1") (pin "19") (pinfunction "PC0_(ADC0/PCINT8)_19") (pintype "bidirectional"))
      (node (ref "U4") (pin "7") (pinfunction "OUT_7") (pintype "output"))
      (node (ref "U4") (pin "8") (pinfunction "-IN_8") (pintype "input"))
    )
    (net (code "54") (name "unconnected-(J2-37-Pad31)") (class "Default")
      (node (ref "J2") (pin "31") (pinfunction "37_31") (pintype "passive"))
    )
    (net (code "55") (name "unconnected-(J2-38-Pad32)") (class "Default")
      (node (ref "J2") (pin "32") (pinfunction "38_32") (pintype "passive"))
    )
    (net (code "56") (name "unconnected-(U1A-(PCINT0{slash}CLKO{slash}ICP1)_PB0-Pad10)") (class "Default")
      (node (ref "U1") (pin "10") (pinfunction "(PCINT0/CLKO/ICP1)_PB0_10") (pintype "bidirectional"))
    )
    (net (code "57") (name "unconnected-(U1A-AREF-Pad17)") (class "Default")
      (node (ref "U1") (pin "17") (pinfunction "AREF_17") (pintype "passive"))
    )
    (net (code "58") (name "unconnected-(U1A-PC2_(ADC2{slash}PCINT10)-Pad21)") (class "Default")
      (node (ref "U1") (pin "21") (pinfunction "PC2_(ADC2/PCINT10)_21") (pintype "bidirectional"))
    )
    (net (code "59") (name "unconnected-(U1A-PC3_(ADC3{slash}PCINT11)-Pad22)") (class "Default")
      (node (ref "U1") (pin "22") (pinfunction "PC3_(ADC3/PCINT11)_22") (pintype "bidirectional"))
    )
  )
)
